# control_panel.net
KiCad netlist of a schematic drawn in EAGLE
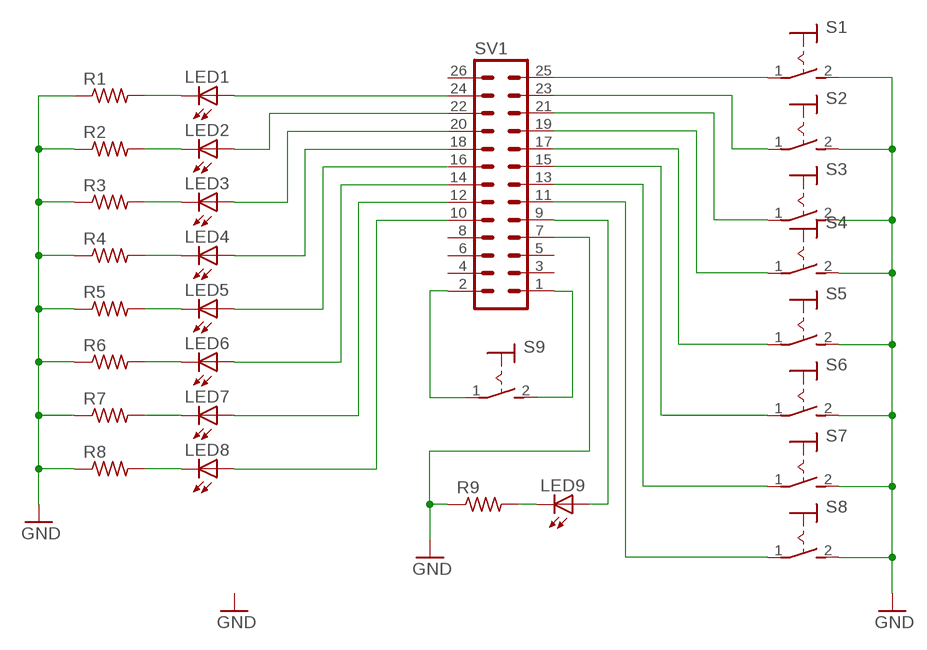
[diagram p0: schematic, sheet 1]

(export (version "E")
  (design (tool "Eeschema 10.0.6"))
  (components
    (comp (ref "LED1")
      (value "LED3MM")
      (footprint "eagle-import:LED3MM")
      (libsource (lib "eagle-import") (part "LED3MM"))
    )
    (comp (ref "LED2")
      (value "LED3MM")
      (footprint "eagle-import:LED3MM")
      (libsource (lib "eagle-import") (part "LED3MM"))
    )
    (comp (ref "LED3")
      (value "LED3MM")
      (footprint "eagle-import:LED3MM")
      (libsource (lib "eagle-import") (part "LED3MM"))
    )
    (comp (ref "LED4")
      (value "LED3MM")
      (footprint "eagle-import:LED3MM")
      (libsource (lib "eagle-import") (part "LED3MM"))
    )
    (comp (ref "LED5")
      (value "LED3MM")
      (footprint "eagle-import:LED3MM")
      (libsource (lib "eagle-import") (part "LED3MM"))
    )
    (comp (ref "LED6")
      (value "LED3MM")
      (footprint "eagle-import:LED3MM")
      (libsource (lib "eagle-import") (part "LED3MM"))
    )
    (comp (ref "LED7")
      (value "LED3MM")
      (footprint "eagle-import:LED3MM")
      (libsource (lib "eagle-import") (part "LED3MM"))
    )
    (comp (ref "LED8")
      (value "LED3MM")
      (footprint "eagle-import:LED3MM")
      (libsource (lib "eagle-import") (part "LED3MM"))
    )
    (comp (ref "LED9")
      (value "LED3MM")
      (footprint "eagle-import:LED3MM")
      (libsource (lib "eagle-import") (part "LED3MM"))
    )
    (comp (ref "R1")
      (value "R-US_0309/12")
      (footprint "eagle-import:0309_12")
      (libsource (lib "eagle-import") (part "R-US_0309/12"))
    )
    (comp (ref "R2")
      (value "R-US_0309/12")
      (footprint "eagle-import:0309_12")
      (libsource (lib "eagle-import") (part "R-US_0309/12"))
    )
    (comp (ref "R3")
      (value "R-US_0309/12")
      (footprint "eagle-import:0309_12")
      (libsource (lib "eagle-import") (part "R-US_0309/12"))
    )
    (comp (ref "R4")
      (value "R-US_0309/12")
      (footprint "eagle-import:0309_12")
      (libsource (lib "eagle-import") (part "R-US_0309/12"))
    )
    (comp (ref "R5")
      (value "R-US_0309/12")
      (footprint "eagle-import:0309_12")
      (libsource (lib "eagle-import") (part "R-US_0309/12"))
    )
    (comp (ref "R6")
      (value "R-US_0309/12")
      (footprint "eagle-import:0309_12")
      (libsource (lib "eagle-import") (part "R-US_0309/12"))
    )
    (comp (ref "R7")
      (value "R-US_0309/12")
      (footprint "eagle-import:0309_12")
      (libsource (lib "eagle-import") (part "R-US_0309/12"))
    )
    (comp (ref "R8")
      (value "R-US_0309/12")
      (footprint "eagle-import:0309_12")
      (libsource (lib "eagle-import") (part "R-US_0309/12"))
    )
    (comp (ref "R9")
      (value "R-US_0309/12")
      (footprint "eagle-import:0309_12")
      (libsource (lib "eagle-import") (part "R-US_0309/12"))
    )
    (comp (ref "S1")
      (value "MS243")
      (footprint "eagle-import:MS243")
      (libsource (lib "eagle-import") (part "MS243"))
    )
    (comp (ref "S2")
      (value "MS243")
      (footprint "eagle-import:MS243")
      (libsource (lib "eagle-import") (part "MS243"))
    )
    (comp (ref "S3")
      (value "MS243")
      (footprint "eagle-import:MS243")
      (libsource (lib "eagle-import") (part "MS243"))
    )
    (comp (ref "S4")
      (value "MS243")
      (footprint "eagle-import:MS243")
      (libsource (lib "eagle-import") (part "MS243"))
    )
    (comp (ref "S5")
      (value "MS243")
      (footprint "eagle-import:MS243")
      (libsource (lib "eagle-import") (part "MS243"))
    )
    (comp (ref "S6")
      (value "MS243")
      (footprint "eagle-import:MS243")
      (libsource (lib "eagle-import") (part "MS243"))
    )
    (comp (ref "S7")
      (value "MS243")
      (footprint "eagle-import:MS243")
      (libsource (lib "eagle-import") (part "MS243"))
    )
    (comp (ref "S8")
      (value "MS243")
      (footprint "eagle-import:MS243")
      (libsource (lib "eagle-import") (part "MS243"))
    )
    (comp (ref "S9")
      (value "MS243")
      (footprint "eagle-import:MS243")
      (libsource (lib "eagle-import") (part "MS243"))
    )
    (comp (ref "SV1")
      (value "MA13-2")
      (footprint "eagle-import:MA13-2")
      (libsource (lib "eagle-import") (part "MA13-2"))
    )
  )
  (nets
    (net (code "1") (name "GND") (class "Default")
      (node (ref "R1") (pin "1") (pinfunction "1_1") (pintype "passive"))
      (node (ref "R2") (pin "1") (pinfunction "1_1") (pintype "passive"))
      (node (ref "R3") (pin "1") (pinfunction "1_1") (pintype "passive"))
      (node (ref "R4") (pin "1") (pinfunction "1_1") (pintype "passive"))
      (node (ref "R5") (pin "1") (pinfunction "1_1") (pintype "passive"))
      (node (ref "R6") (pin "1") (pinfunction "1_1") (pintype "passive"))
      (node (ref "R7") (pin "1") (pinfunction "1_1") (pintype "passive"))
      (node (ref "R8") (pin "1") (pinfunction "1_1") (pintype "passive"))
      (node (ref "R9") (pin "1") (pinfunction "1_1") (pintype "passive"))
      (node (ref "S1") (pin "2") (pinfunction "S_2") (pintype "passive"))
      (node (ref "S2") (pin "2") (pinfunction "S_2") (pintype "passive"))
      (node (ref "S3") (pin "2") (pinfunction "S_2") (pintype "passive"))
      (node (ref "S4") (pin "2") (pinfunction "S_2") (pintype "passive"))
      (node (ref "S5") (pin "2") (pinfunction "S_2") (pintype "passive"))
      (node (ref "S6") (pin "2") (pinfunction "S_2") (pintype "passive"))
      (node (ref "S7") (pin "2") (pinfunction "S_2") (pintype "passive"))
      (node (ref "S8") (pin "2") (pinfunction "S_2") (pintype "passive"))
      (node (ref "SV1") (pin "7") (pinfunction "7_7") (pintype "passive"))
    )
    (net (code "2") (name "Net-(LED1-C)") (class "Default")
      (node (ref "LED1") (pin "K") (pinfunction "C_K") (pintype "passive"))
      (node (ref "R1") (pin "2") (pinfunction "2_2") (pintype "passive"))
    )
    (net (code "3") (name "Net-(LED1-PadA)") (class "Default")
      (node (ref "LED1") (pin "A") (pinfunction "A_A") (pintype "passive"))
      (node (ref "SV1") (pin "24") (pinfunction "24_24") (pintype "passive"))
    )
    (net (code "4") (name "Net-(LED2-C)") (class "Default")
      (node (ref "LED2") (pin "K") (pinfunction "C_K") (pintype "passive"))
      (node (ref "R2") (pin "2") (pinfunction "2_2") (pintype "passive"))
    )
    (net (code "5") (name "Net-(LED2-PadA)") (class "Default")
      (node (ref "LED2") (pin "A") (pinfunction "A_A") (pintype "passive"))
      (node (ref "SV1") (pin "22") (pinfunction "22_22") (pintype "passive"))
    )
    (net (code "6") (name "Net-(LED3-C)") (class "Default")
      (node (ref "LED3") (pin "K") (pinfunction "C_K") (pintype "passive"))
      (node (ref "R3") (pin "2") (pinfunction "2_2") (pintype "passive"))
    )
    (net (code "7") (name "Net-(LED3-PadA)") (class "Default")
      (node (ref "LED3") (pin "A") (pinfunction "A_A") (pintype "passive"))
      (node (ref "SV1") (pin "20") (pinfunction "20_20") (pintype "passive"))
    )
    (net (code "8") (name "Net-(LED4-C)") (class "Default")
      (node (ref "LED4") (pin "K") (pinfunction "C_K") (pintype "passive"))
      (node (ref "R4") (pin "2") (pinfunction "2_2") (pintype "passive"))
    )
    (net (code "9") (name "Net-(LED4-PadA)") (class "Default")
      (node (ref "LED4") (pin "A") (pinfunction "A_A") (pintype "passive"))
      (node (ref "SV1") (pin "18") (pinfunction "18_18") (pintype "passive"))
    )
    (net (code "10") (name "Net-(LED5-C)") (class "Default")
      (node (ref "LED5") (pin "K") (pinfunction "C_K") (pintype "passive"))
      (node (ref "R5") (pin "2") (pinfunction "2_2") (pintype "passive"))
    )
    (net (code "11") (name "Net-(LED5-PadA)") (class "Default")
      (node (ref "LED5") (pin "A") (pinfunction "A_A") (pintype "passive"))
      (node (ref "SV1") (pin "16") (pinfunction "16_16") (pintype "passive"))
    )
    (net (code "12") (name "Net-(LED6-C)") (class "Default")
      (node (ref "LED6") (pin "K") (pinfunction "C_K") (pintype "passive"))
      (node (ref "R6") (pin "2") (pinfunction "2_2") (pintype "passive"))
    )
    (net (code "13") (name "Net-(LED6-PadA)") (class "Default")
      (node (ref "LED6") (pin "A") (pinfunction "A_A") (pintype "passive"))
      (node (ref "SV1") (pin "14") (pinfunction "14_14") (pintype "passive"))
    )
    (net (code "14") (name "Net-(LED7-C)") (class "Default")
      (node (ref "LED7") (pin "K") (pinfunction "C_K") (pintype "passive"))
      (node (ref "R7") (pin "2") (pinfunction "2_2") (pintype "passive"))
    )
    (net (code "15") (name "Net-(LED7-PadA)") (class "Default")
      (node (ref "LED7") (pin "A") (pinfunction "A_A") (pintype "passive"))
      (node (ref "SV1") (pin "12") (pinfunction "12_12") (pintype "passive"))
    )
    (net (code "16") (name "Net-(LED8-C)") (class "Default")
      (node (ref "LED8") (pin "K") (pinfunction "C_K") (pintype "passive"))
      (node (ref "R8") (pin "2") (pinfunction "2_2") (pintype "passive"))
    )
    (net (code "17") (name "Net-(LED8-PadA)") (class "Default")
      (node (ref "LED8") (pin "A") (pinfunction "A_A") (pintype "passive"))
      (node (ref "SV1") (pin "10") (pinfunction "10_10") (pintype "passive"))
    )
    (net (code "18") (name "Net-(LED9-C)") (class "Default")
      (node (ref "LED9") (pin "K") (pinfunction "C_K") (pintype "passive"))
      (node (ref "R9") (pin "2") (pinfunction "2_2") (pintype "passive"))
    )
    (net (code "19") (name "Net-(LED9-PadA)") (class "Default")
      (node (ref "LED9") (pin "A") (pinfunction "A_A") (pintype "passive"))
      (node (ref "SV1") (pin "9") (pinfunction "9_9") (pintype "passive"))
    )
    (net (code "20") (name "Net-(S1-P)") (class "Default")
      (node (ref "S1") (pin "1") (pinfunction "P_1") (pintype "passive"))
      (node (ref "SV1") (pin "25") (pinfunction "25_25") (pintype "passive"))
    )
    (net (code "21") (name "Net-(S2-P)") (class "Default")
      (node (ref "S2") (pin "1") (pinfunction "P_1") (pintype "passive"))
      (node (ref "SV1") (pin "23") (pinfunction "23_23") (pintype "passive"))
    )
    (net (code "22") (name "Net-(S3-P)") (class "Default")
      (node (ref "S3") (pin "1") (pinfunction "P_1") (pintype "passive"))
      (node (ref "SV1") (pin "21") (pinfunction "21_21") (pintype "passive"))
    )
    (net (code "23") (name "Net-(S4-P)") (class "Default")
      (node (ref "S4") (pin "1") (pinfunction "P_1") (pintype "passive"))
      (node (ref "SV1") (pin "19") (pinfunction "19_19") (pintype "passive"))
    )
    (net (code "24") (name "Net-(S5-P)") (class "Default")
      (node (ref "S5") (pin "1") (pinfunction "P_1") (pintype "passive"))
      (node (ref "SV1") (pin "17") (pinfunction "17_17") (pintype "passive"))
    )
    (net (code "25") (name "Net-(S6-P)") (class "Default")
      (node (ref "S6") (pin "1") (pinfunction "P_1") (pintype "passive"))
      (node (ref "SV1") (pin "15") (pinfunction "15_15") (pintype "passive"))
    )
    (net (code "26") (name "Net-(S7-P)") (class "Default")
      (node (ref "S7") (pin "1") (pinfunction "P_1") (pintype "passive"))
      (node (ref "SV1") (pin "13") (pinfunction "13_13") (pintype "passive"))
    )
    (net (code "27") (name "Net-(S8-P)") (class "Default")
      (node (ref "S8") (pin "1") (pinfunction "P_1") (pintype "passive"))
      (node (ref "SV1") (pin "11") (pinfunction "11_11") (pintype "passive"))
    )
    (net (code "28") (name "Net-(S9-P)") (class "Default")
      (node (ref "S9") (pin "1") (pinfunction "P_1") (pintype "passive"))
      (node (ref "SV1") (pin "2") (pinfunction "2_2") (pintype "passive"))
    )
    (net (code "29") (name "Net-(S9-S)") (class "Default")
      (node (ref "S9") (pin "2") (pinfunction "S_2") (pintype "passive"))
      (node (ref "SV1") (pin "1") (pinfunction "1_1") (pintype "passive"))
    )
    (net (code "30") (name "unconnected-(SV1-Pad3)") (class "Default")
      (node (ref "SV1") (pin "3") (pinfunction "3_3") (pintype "passive"))
    )
    (net (code "31") (name "unconnected-(SV1-Pad4)") (class "Default")
      (node (ref "SV1") (pin "4") (pinfunction "4_4") (pintype "passive"))
    )
    (net (code "32") (name "unconnected-(SV1-Pad5)") (class "Default")
      (node (ref "SV1") (pin "5") (pinfunction "5_5") (pintype "passive"))
    )
    (net (code "33") (name "unconnected-(SV1-Pad6)") (class "Default")
      (node (ref "SV1") (pin "6") (pinfunction "6_6") (pintype "passive"))
    )
    (net (code "34") (name "unconnected-(SV1-Pad8)") (class "Default")
      (node (ref "SV1") (pin "8") (pinfunction "8_8") (pintype "passive"))
    )
    (net (code "35") (name "unconnected-(SV1-Pad26)") (class "Default")
      (node (ref "SV1") (pin "26") (pinfunction "26_26") (pintype "passive"))
    )
  )
)
